# MAIN.net
KiCad netlist of a schematic drawn in Altium Designer
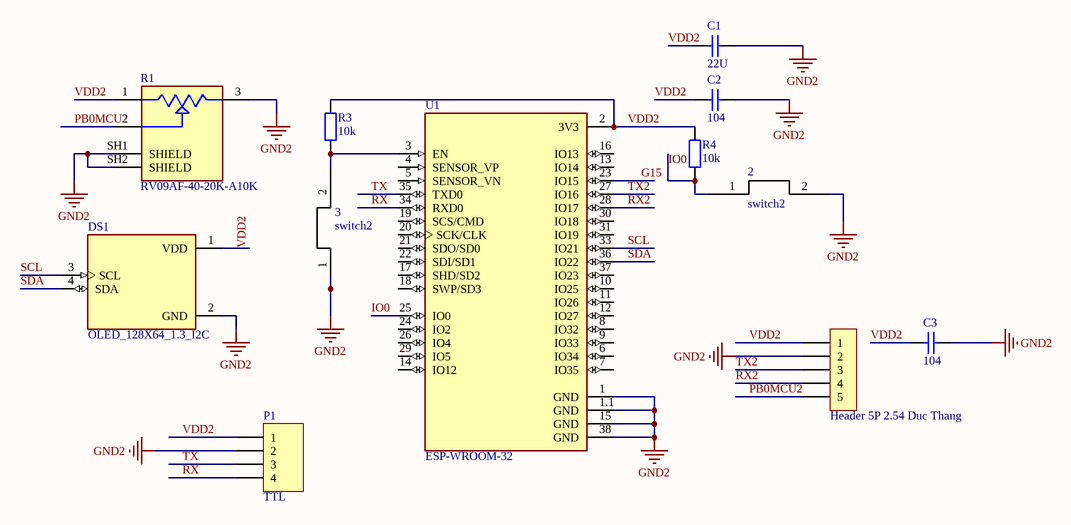
[diagram p0: MAIN.SchDoc]

(export (version "E")
  (design (tool "Eeschema 10.0.6"))
  (components
    (comp (ref "2") (value "switch2") (footprint "switch") (libsource (lib "TV1") (part "switch2")))
    (comp (ref "3") (value "switch2") (footprint "switch") (libsource (lib "TV1") (part "switch2")))
    (comp (ref "C1")
      (value "22U")
      (footprint "tu 0805")
      (description "Dán")
      (libsource (lib "Altium_Lib_by_KhueNguyenCreator") (part "Tu 0805 225 25V 10%"))
    )
    (comp (ref "C2")
      (value "104")
      (footprint "tu 0805")
      (description "Dán")
      (libsource (lib "Altium_Lib_by_KhueNguyenCreator") (part "Tu 0805 104 50V 10%"))
    )
    (comp (ref "C3")
      (value "104")
      (footprint "tu 0805")
      (description "Dán")
      (libsource (lib "Altium_Lib_by_KhueNguyenCreator") (part "Tu 0805 104 50V 10%"))
    )
    (comp (ref "DS1")
      (value "OLED_128X64_1.3_I2C")
      (footprint "LCD_OLED_128X64_1.3_I2C - duplicate")
      (fields
        (field (name "MF") "UNIVERSAL-SOLDER Electronics Ltd")
        (field (name "MP") "OLED 128x64 1.3&quot; I2C")
      )
      (libsource (lib "TV1") (part "OLED_128X64_1.3_I2C"))
    )
    (comp (ref "H1")
      (value "Header 5P 2.54 Duc Thang")
      (footprint "XH2.54M-5")
      (description "Cắm")
      (libsource (lib "Altium_Lib_by_KhueNguyenCreator") (part "Header 5P 2.54 Duc Thang"))
    )
    (comp (ref "P1")
      (value "TTL")
      (footprint "HDR1X4")
      (description "Header, 4-Pin")
      (fields (field (name "PUBLISHER") "Altium Limited"))
      (libsource (lib "Miscellaneous Connectors") (part "Header 4"))
    )
    (comp (ref "R1")
      (value "RV09AF-40-20K-A10K")
      (footprint "TRIM_RV09AF-40-20K-A10K")
      (description "PC Mount Black Shaft Potentiometers Audio 9mm 10K")
      (fields (field (name "MF") "Alpha Taiwan"))
      (libsource (lib "TV1") (part "RV09AF-40-20K-A10K"))
    )
    (comp (ref "R3")
      (value "10k")
      (footprint "tro smd 0805")
      (description "Dán")
      (libsource (lib "Altium_Lib_by_KhueNguyenCreator") (part "Tro 0805 1% 0.33R"))
    )
    (comp (ref "R4")
      (value "10k")
      (footprint "tro smd 0805")
      (description "Dán")
      (libsource (lib "Altium_Lib_by_KhueNguyenCreator") (part "Tro 0805 1% 0.33R"))
    )
    (comp (ref "U1")
      (value "ESP-WROOM-32")
      (footprint "MODULE_ESP-WROOM-32")
      (fields (field (name "MF") "Espressif Systems"))
      (libsource (lib "TV1") (part "ESP-WROOM-32"))
    )
  )
  (nets
    (net (code "1") (name "/G15") (class "Default")
      (node (ref "U1") (pin "23") (pinfunction "IO15_23") (pintype "bidirectional"))
    )
    (net (code "2") (name "/IO0") (class "Default")
      (node (ref "2") (pin "1") (pintype "passive"))
      (node (ref "R4") (pin "1") (pinfunction "1_1") (pintype "passive"))
      (node (ref "U1") (pin "25") (pinfunction "IO0_25") (pintype "bidirectional"))
    )
    (net (code "3") (name "/PB0MCU2") (class "Default")
      (node (ref "H1") (pin "5") (pinfunction "5_5") (pintype "passive"))
      (node (ref "R1") (pin "2") (pinfunction "2_2") (pintype "passive"))
    )
    (net (code "4") (name "/RX") (class "Default")
      (node (ref "P1") (pin "4") (pinfunction "4_4") (pintype "passive"))
      (node (ref "U1") (pin "34") (pinfunction "RXD0_34") (pintype "bidirectional"))
    )
    (net (code "5") (name "/RX2") (class "Default")
      (node (ref "H1") (pin "4") (pinfunction "4_4") (pintype "passive"))
      (node (ref "U1") (pin "28") (pinfunction "IO17_28") (pintype "bidirectional"))
    )
    (net (code "6") (name "/SCL") (class "Default")
      (node (ref "DS1") (pin "3") (pinfunction "SCL_3") (pintype "input"))
      (node (ref "U1") (pin "33") (pinfunction "IO21_33") (pintype "bidirectional"))
    )
    (net (code "7") (name "/SDA") (class "Default")
      (node (ref "DS1") (pin "4") (pinfunction "SDA_4") (pintype "bidirectional"))
      (node (ref "U1") (pin "36") (pinfunction "IO22_36") (pintype "bidirectional"))
    )
    (net (code "8") (name "/TX") (class "Default")
      (node (ref "P1") (pin "3") (pinfunction "3_3") (pintype "passive"))
      (node (ref "U1") (pin "35") (pinfunction "TXD0_35") (pintype "bidirectional"))
    )
    (net (code "9") (name "/TX2") (class "Default")
      (node (ref "H1") (pin "3") (pinfunction "3_3") (pintype "passive"))
      (node (ref "U1") (pin "27") (pinfunction "IO16_27") (pintype "bidirectional"))
    )
    (net (code "10") (name "/VDD2") (class "Default")
      (node (ref "C1") (pin "2") (pinfunction "2_2") (pintype "passive"))
      (node (ref "C2") (pin "2") (pinfunction "2_2") (pintype "passive"))
      (node (ref "C3") (pin "2") (pinfunction "2_2") (pintype "passive"))
      (node (ref "DS1") (pin "1") (pinfunction "VDD_1") (pintype "power_in"))
      (node (ref "H1") (pin "1") (pinfunction "1_1") (pintype "passive"))
      (node (ref "P1") (pin "1") (pinfunction "1_1") (pintype "passive"))
      (node (ref "R1") (pin "1") (pinfunction "1_1") (pintype "passive"))
      (node (ref "R3") (pin "1") (pinfunction "1_1") (pintype "passive"))
      (node (ref "R4") (pin "2") (pinfunction "2_2") (pintype "passive"))
      (node (ref "U1") (pin "2") (pinfunction "3V3_2") (pintype "power_in"))
    )
    (net (code "11") (name "GND2") (class "Default")
      (node (ref "2") (pin "2") (pintype "passive"))
      (node (ref "3") (pin "1") (pintype "passive"))
      (node (ref "C1") (pin "1") (pinfunction "1_1") (pintype "passive"))
      (node (ref "C2") (pin "1") (pinfunction "1_1") (pintype "passive"))
      (node (ref "C3") (pin "1") (pinfunction "1_1") (pintype "passive"))
      (node (ref "DS1") (pin "2") (pinfunction "GND_2") (pintype "power_in"))
      (node (ref "H1") (pin "2") (pinfunction "2_2") (pintype "passive"))
      (node (ref "P1") (pin "2") (pinfunction "2_2") (pintype "passive"))
      (node (ref "R1") (pin "3") (pinfunction "3_3") (pintype "passive"))
      (node (ref "R1") (pin "SH1") (pinfunction "SHIELD_SH1") (pintype "passive"))
      (node (ref "R1") (pin "SH2") (pinfunction "SHIELD_SH2") (pintype "passive"))
      (node (ref "U1") (pin "1") (pinfunction "GND_1") (pintype "power_in"))
      (node (ref "U1") (pin "1.1") (pinfunction "GND_1.1") (pintype "power_in"))
      (node (ref "U1") (pin "15") (pinfunction "GND_15") (pintype "power_in"))
      (node (ref "U1") (pin "38") (pinfunction "GND_38") (pintype "power_in"))
    )
    (net (code "12") (name "Net-(U1-EN)") (class "Default")
      (node (ref "3") (pin "2") (pintype "passive"))
      (node (ref "R3") (pin "2") (pinfunction "2_2") (pintype "passive"))
      (node (ref "U1") (pin "3") (pinfunction "EN_3") (pintype "input"))
    )
    (net (code "13") (name "unconnected-(U1-IO2-Pad24)") (class "Default")
      (node (ref "U1") (pin "24") (pinfunction "IO2_24") (pintype "bidirectional"))
    )
    (net (code "14") (name "unconnected-(U1-IO4-Pad26)") (class "Default")
      (node (ref "U1") (pin "26") (pinfunction "IO4_26") (pintype "bidirectional"))
    )
    (net (code "15") (name "unconnected-(U1-IO5-Pad29)") (class "Default")
      (node (ref "U1") (pin "29") (pinfunction "IO5_29") (pintype "bidirectional"))
    )
    (net (code "16") (name "unconnected-(U1-IO12-Pad14)") (class "Default")
      (node (ref "U1") (pin "14") (pinfunction "IO12_14") (pintype "bidirectional"))
    )
    (net (code "17") (name "unconnected-(U1-IO13-Pad16)") (class "Default")
      (node (ref "U1") (pin "16") (pinfunction "IO13_16") (pintype "bidirectional"))
    )
    (net (code "18") (name "unconnected-(U1-IO14-Pad13)") (class "Default")
      (node (ref "U1") (pin "13") (pinfunction "IO14_13") (pintype "bidirectional"))
    )
    (net (code "19") (name "unconnected-(U1-IO18-Pad30)") (class "Default")
      (node (ref "U1") (pin "30") (pinfunction "IO18_30") (pintype "bidirectional"))
    )
    (net (code "20") (name "unconnected-(U1-IO19-Pad31)") (class "Default")
      (node (ref "U1") (pin "31") (pinfunction "IO19_31") (pintype "bidirectional"))
    )
    (net (code "21") (name "unconnected-(U1-IO23-Pad37)") (class "Default")
      (node (ref "U1") (pin "37") (pinfunction "IO23_37") (pintype "bidirectional"))
    )
    (net (code "22") (name "unconnected-(U1-IO25-Pad10)") (class "Default")
      (node (ref "U1") (pin "10") (pinfunction "IO25_10") (pintype "bidirectional"))
    )
    (net (code "23") (name "unconnected-(U1-IO26-Pad11)") (class "Default")
      (node (ref "U1") (pin "11") (pinfunction "IO26_11") (pintype "bidirectional"))
    )
    (net (code "24") (name "unconnected-(U1-IO27-Pad12)") (class "Default")
      (node (ref "U1") (pin "12") (pinfunction "IO27_12") (pintype "bidirectional"))
    )
    (net (code "25") (name "unconnected-(U1-IO32-Pad8)") (class "Default")
      (node (ref "U1") (pin "8") (pinfunction "IO32_8") (pintype "bidirectional"))
    )
    (net (code "26") (name "unconnected-(U1-IO33-Pad9)") (class "Default")
      (node (ref "U1") (pin "9") (pinfunction "IO33_9") (pintype "bidirectional"))
    )
    (net (code "27") (name "unconnected-(U1-IO34-Pad6)") (class "Default")
      (node (ref "U1") (pin "6") (pinfunction "IO34_6") (pintype "bidirectional"))
    )
    (net (code "28") (name "unconnected-(U1-IO35-Pad7)") (class "Default")
      (node (ref "U1") (pin "7") (pinfunction "IO35_7") (pintype "bidirectional"))
    )
    (net (code "29") (name "unconnected-(U1-SCK{slash}CLK-Pad20)") (class "Default")
      (node (ref "U1") (pin "20") (pinfunction "SCK/CLK_20") (pintype "bidirectional"))
    )
    (net (code "30") (name "unconnected-(U1-SCS{slash}CMD-Pad19)") (class "Default")
      (node (ref "U1") (pin "19") (pinfunction "SCS/CMD_19") (pintype "bidirectional"))
    )
    (net (code "31") (name "unconnected-(U1-SDI{slash}SD1-Pad22)") (class "Default")
      (node (ref "U1") (pin "22") (pinfunction "SDI/SD1_22") (pintype "bidirectional"))
    )
    (net (code "32") (name "unconnected-(U1-SDO{slash}SD0-Pad21)") (class "Default")
      (node (ref "U1") (pin "21") (pinfunction "SDO/SD0_21") (pintype "bidirectional"))
    )
    (net (code "33") (name "unconnected-(U1-SENSOR_VN-Pad5)") (class "Default")
      (node (ref "U1") (pin "5") (pinfunction "SENSOR_VN_5") (pintype "input"))
    )
    (net (code "34") (name "unconnected-(U1-SENSOR_VP-Pad4)") (class "Default")
      (node (ref "U1") (pin "4") (pinfunction "SENSOR_VP_4") (pintype "input"))
    )
    (net (code "35") (name "unconnected-(U1-SHD{slash}SD2-Pad17)") (class "Default")
      (node (ref "U1") (pin "17") (pinfunction "SHD/SD2_17") (pintype "bidirectional"))
    )
    (net (code "36") (name "unconnected-(U1-SWP{slash}SD3-Pad18)") (class "Default")
      (node (ref "U1") (pin "18") (pinfunction "SWP/SD3_18") (pintype "bidirectional"))
    )
  )
)
